# astable.net
KiCad netlist of a schematic drawn in EAGLE
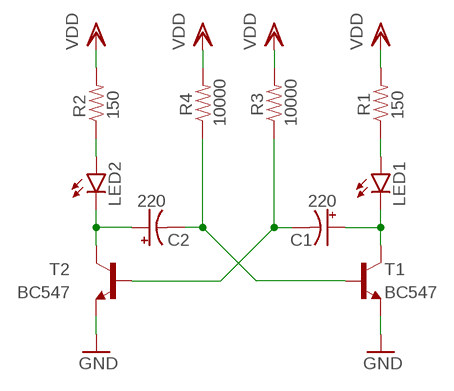
[diagram p0: schematic, sheet 1]

(export (version "E")
  (design (tool "Eeschema 10.0.6"))
  (components
    (comp (ref "C1")
      (value "220")
      (footprint "eagle-import:CPOL-RADIAL-1000UF-25V")
      (libsource (lib "eagle-import") (part "CAP_POLPTH4"))
    )
    (comp (ref "C2")
      (value "220")
      (footprint "eagle-import:CPOL-RADIAL-1000UF-25V")
      (libsource (lib "eagle-import") (part "CAP_POLPTH4"))
    )
    (comp (ref "LED1")
      (value "LED5MM")
      (footprint "eagle-import:LED5MM")
      (libsource (lib "eagle-import") (part "LED5MM"))
    )
    (comp (ref "LED2")
      (value "LED5MM")
      (footprint "eagle-import:LED5MM")
      (libsource (lib "eagle-import") (part "LED5MM"))
    )
    (comp (ref "R1")
      (value "150")
      (footprint "eagle-import:AXIAL-0.5")
      (libsource (lib "eagle-import") (part "RESISTORPTH-1/2W"))
    )
    (comp (ref "R2")
      (value "150")
      (footprint "eagle-import:AXIAL-0.5")
      (libsource (lib "eagle-import") (part "RESISTORPTH-1/2W"))
    )
    (comp (ref "R3")
      (value "10000")
      (footprint "eagle-import:AXIAL-0.5")
      (libsource (lib "eagle-import") (part "RESISTORPTH-1/2W"))
    )
    (comp (ref "R4")
      (value "10000")
      (footprint "eagle-import:AXIAL-0.5")
      (libsource (lib "eagle-import") (part "RESISTORPTH-1/2W"))
    )
    (comp (ref "T1")
      (value "BC547")
      (footprint "eagle-import:TO92")
      (libsource (lib "eagle-import") (part "BC547"))
    )
    (comp (ref "T2")
      (value "BC547")
      (footprint "eagle-import:TO92")
      (libsource (lib "eagle-import") (part "BC547"))
    )
  )
  (nets
    (net (code "1") (name "GND") (class "Default")
      (node (ref "T1") (pin "1") (pinfunction "E_1") (pintype "passive"))
      (node (ref "T2") (pin "1") (pinfunction "E_1") (pintype "passive"))
    )
    (net (code "2") (name "Net-(C1-+)") (class "Default")
      (node (ref "C1") (pin "1") (pinfunction "+_1") (pintype "passive"))
      (node (ref "LED1") (pin "K") (pinfunction "C_K") (pintype "passive"))
      (node (ref "T1") (pin "3") (pinfunction "C_3") (pintype "passive"))
    )
    (net (code "3") (name "Net-(C1--)") (class "Default")
      (node (ref "C1") (pin "2") (pinfunction "-_2") (pintype "passive"))
      (node (ref "R3") (pin "P$1") (pinfunction "1_P$1") (pintype "passive"))
      (node (ref "T2") (pin "2") (pinfunction "B_2") (pintype "passive"))
    )
    (net (code "4") (name "Net-(C2-+)") (class "Default")
      (node (ref "C2") (pin "1") (pinfunction "+_1") (pintype "passive"))
      (node (ref "LED2") (pin "K") (pinfunction "C_K") (pintype "passive"))
      (node (ref "T2") (pin "3") (pinfunction "C_3") (pintype "passive"))
    )
    (net (code "5") (name "Net-(C2--)") (class "Default")
      (node (ref "C2") (pin "2") (pinfunction "-_2") (pintype "passive"))
      (node (ref "R4") (pin "P$1") (pinfunction "1_P$1") (pintype "passive"))
      (node (ref "T1") (pin "2") (pinfunction "B_2") (pintype "passive"))
    )
    (net (code "6") (name "Net-(R1-1)") (class "Default")
      (node (ref "LED1") (pin "A") (pinfunction "A_A") (pintype "passive"))
      (node (ref "R1") (pin "P$1") (pinfunction "1_P$1") (pintype "passive"))
    )
    (net (code "7") (name "Net-(R2-1)") (class "Default")
      (node (ref "LED2") (pin "A") (pinfunction "A_A") (pintype "passive"))
      (node (ref "R2") (pin "P$1") (pinfunction "1_P$1") (pintype "passive"))
    )
    (net (code "8") (name "VDD") (class "Default")
      (node (ref "R1") (pin "P$2") (pinfunction "2_P$2") (pintype "passive"))
      (node (ref "R2") (pin "P$2") (pinfunction "2_P$2") (pintype "passive"))
      (node (ref "R3") (pin "P$2") (pinfunction "2_P$2") (pintype "passive"))
      (node (ref "R4") (pin "P$2") (pinfunction "2_P$2") (pintype "passive"))
    )
  )
)
